# board.net
KiCad netlist of a schematic drawn in EAGLE
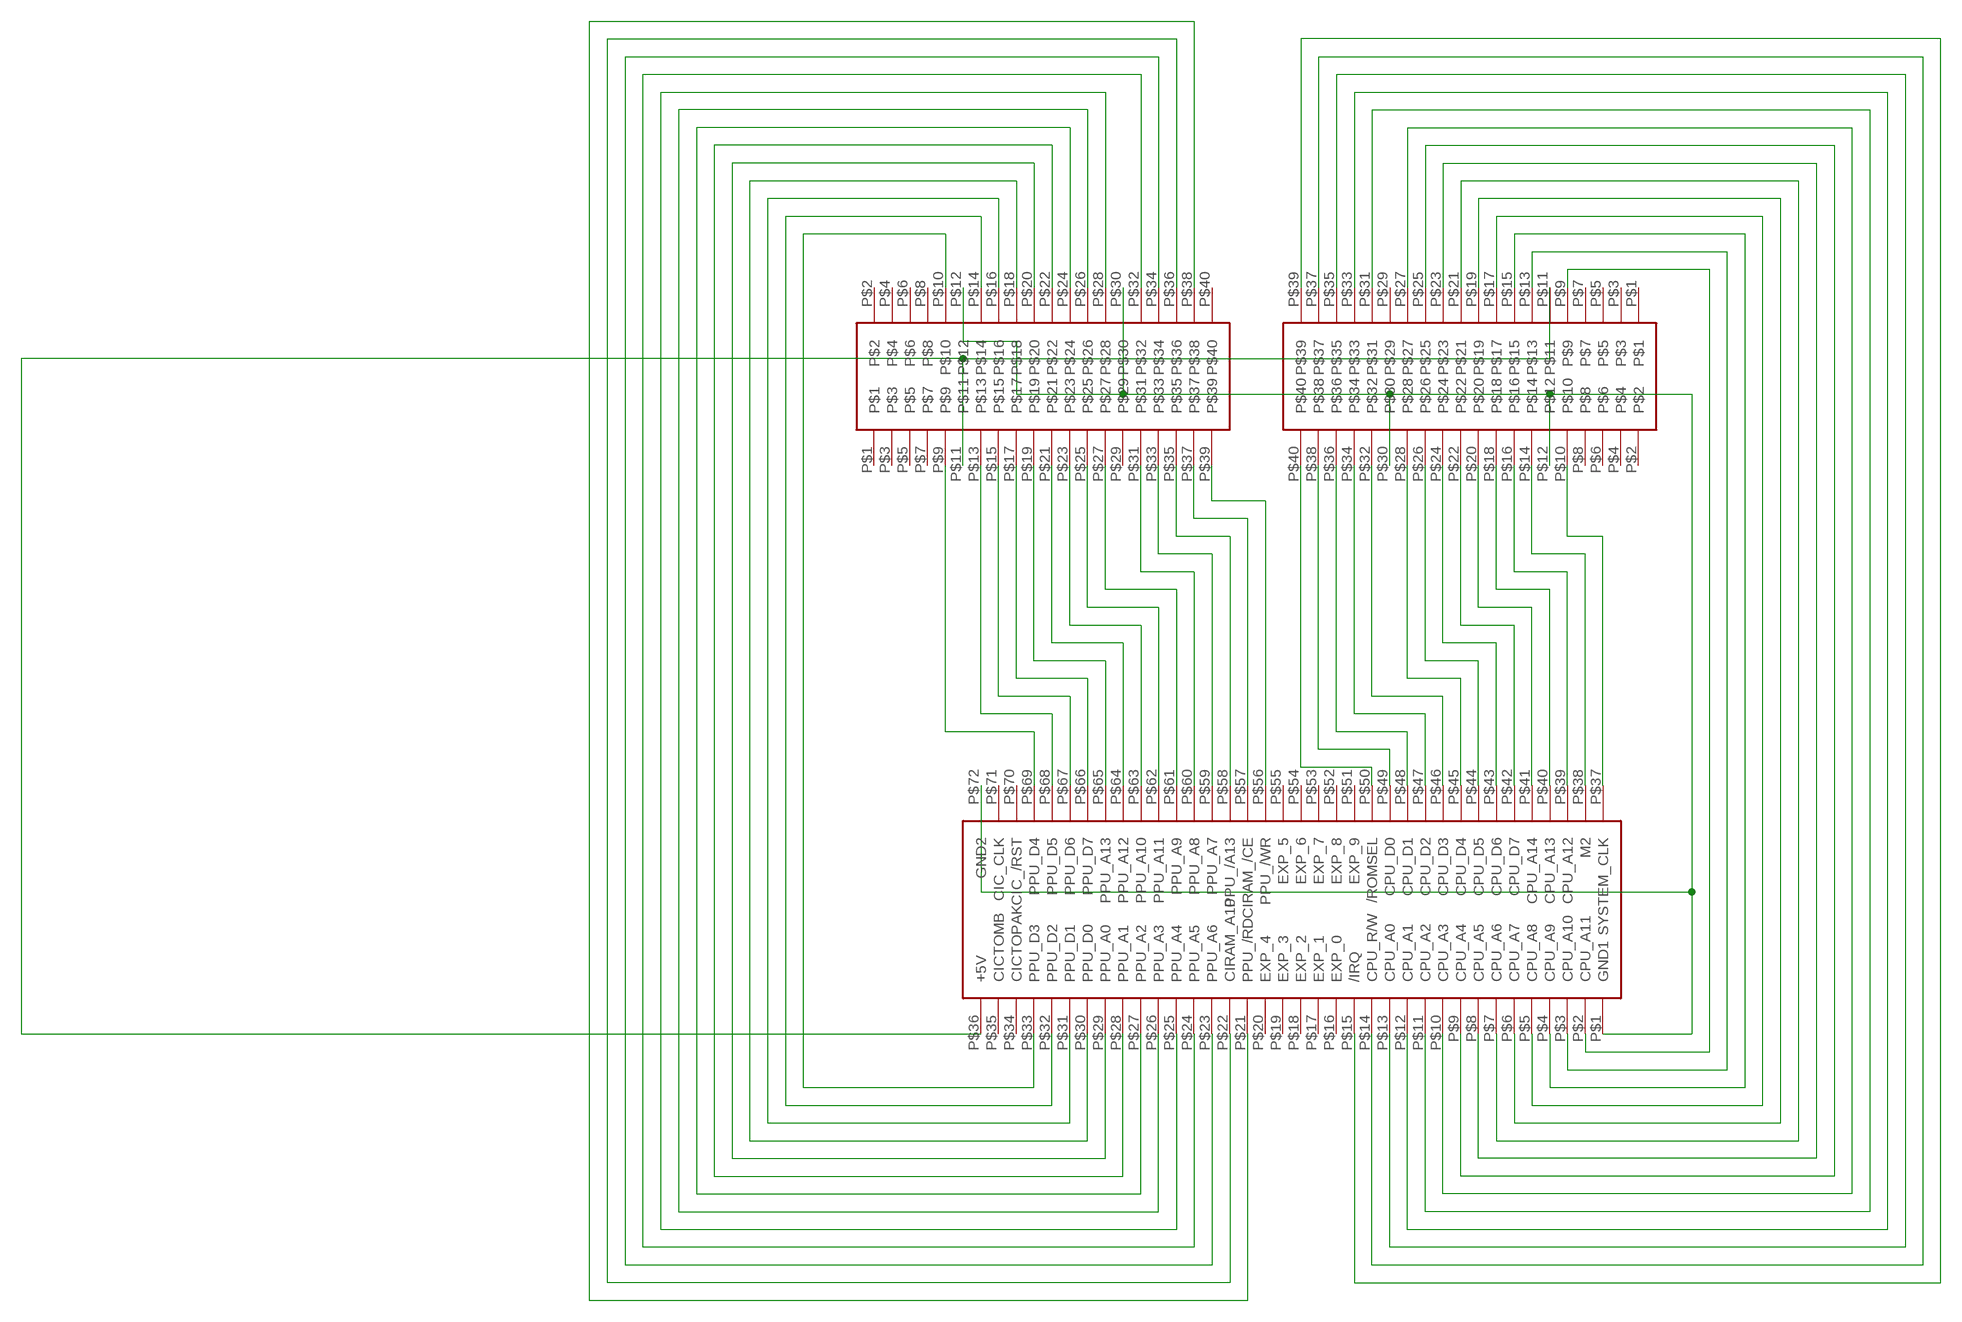
[diagram p0: schematic, sheet 1]

(export (version "E")
  (design (tool "Eeschema 10.0.6"))
  (components
    (comp (ref "U$1")
      (value "NES_CONN")
      (footprint "eagle-import:36X2")
      (libsource (lib "eagle-import") (part "NES_CONN"))
    )
    (comp (ref "U$2")
      (value "40PINNER")
      (footprint "eagle-import:40PINNER")
      (libsource (lib "eagle-import") (part "40PINNER"))
    )
    (comp (ref "U$3")
      (value "40PINNER")
      (footprint "eagle-import:40PINNER")
      (libsource (lib "eagle-import") (part "40PINNER"))
    )
  )
  (nets
    (net (code "1") (name "Net-(U$1-+5V)") (class "Default")
      (node (ref "U$1") (pin "P$36") (pinfunction "+5V_P$36") (pintype "bidirectional"))
      (node (ref "U$2") (pin "P$11") (pinfunction "P$11_P$11") (pintype "bidirectional"))
      (node (ref "U$3") (pin "P$11") (pinfunction "P$11_P$11") (pintype "bidirectional"))
    )
    (net (code "2") (name "Net-(U$1-CIRAM_A10)") (class "Default")
      (node (ref "U$1") (pin "P$22") (pinfunction "CIRAM_A10_P$22") (pintype "bidirectional"))
      (node (ref "U$2") (pin "P$36") (pinfunction "P$36_P$36") (pintype "bidirectional"))
    )
    (net (code "3") (name "Net-(U$1-CIRAM_{slash}CE)") (class "Default")
      (node (ref "U$1") (pin "P$57") (pinfunction "CIRAM_/CE_P$57") (pintype "bidirectional"))
      (node (ref "U$2") (pin "P$37") (pinfunction "P$37_P$37") (pintype "bidirectional"))
    )
    (net (code "4") (name "Net-(U$1-CPU_A0)") (class "Default")
      (node (ref "U$1") (pin "P$13") (pinfunction "CPU_A0_P$13") (pintype "bidirectional"))
      (node (ref "U$3") (pin "P$35") (pinfunction "P$35_P$35") (pintype "bidirectional"))
    )
    (net (code "5") (name "Net-(U$1-CPU_A1)") (class "Default")
      (node (ref "U$1") (pin "P$12") (pinfunction "CPU_A1_P$12") (pintype "bidirectional"))
      (node (ref "U$3") (pin "P$33") (pinfunction "P$33_P$33") (pintype "bidirectional"))
    )
    (net (code "6") (name "Net-(U$1-CPU_A2)") (class "Default")
      (node (ref "U$1") (pin "P$11") (pinfunction "CPU_A2_P$11") (pintype "bidirectional"))
      (node (ref "U$3") (pin "P$31") (pinfunction "P$31_P$31") (pintype "bidirectional"))
    )
    (net (code "7") (name "Net-(U$1-CPU_A3)") (class "Default")
      (node (ref "U$1") (pin "P$10") (pinfunction "CPU_A3_P$10") (pintype "bidirectional"))
      (node (ref "U$3") (pin "P$27") (pinfunction "P$27_P$27") (pintype "bidirectional"))
    )
    (net (code "8") (name "Net-(U$1-CPU_A4)") (class "Default")
      (node (ref "U$1") (pin "P$9") (pinfunction "CPU_A4_P$9") (pintype "bidirectional"))
      (node (ref "U$3") (pin "P$25") (pinfunction "P$25_P$25") (pintype "bidirectional"))
    )
    (net (code "9") (name "Net-(U$1-CPU_A5)") (class "Default")
      (node (ref "U$1") (pin "P$8") (pinfunction "CPU_A5_P$8") (pintype "bidirectional"))
      (node (ref "U$3") (pin "P$23") (pinfunction "P$23_P$23") (pintype "bidirectional"))
    )
    (net (code "10") (name "Net-(U$1-CPU_A6)") (class "Default")
      (node (ref "U$1") (pin "P$7") (pinfunction "CPU_A6_P$7") (pintype "bidirectional"))
      (node (ref "U$3") (pin "P$21") (pinfunction "P$21_P$21") (pintype "bidirectional"))
    )
    (net (code "11") (name "Net-(U$1-CPU_A7)") (class "Default")
      (node (ref "U$1") (pin "P$6") (pinfunction "CPU_A7_P$6") (pintype "bidirectional"))
      (node (ref "U$3") (pin "P$19") (pinfunction "P$19_P$19") (pintype "bidirectional"))
    )
    (net (code "12") (name "Net-(U$1-CPU_A8)") (class "Default")
      (node (ref "U$1") (pin "P$5") (pinfunction "CPU_A8_P$5") (pintype "bidirectional"))
      (node (ref "U$3") (pin "P$17") (pinfunction "P$17_P$17") (pintype "bidirectional"))
    )
    (net (code "13") (name "Net-(U$1-CPU_A9)") (class "Default")
      (node (ref "U$1") (pin "P$4") (pinfunction "CPU_A9_P$4") (pintype "bidirectional"))
      (node (ref "U$3") (pin "P$15") (pinfunction "P$15_P$15") (pintype "bidirectional"))
    )
    (net (code "14") (name "Net-(U$1-CPU_A10)") (class "Default")
      (node (ref "U$1") (pin "P$3") (pinfunction "CPU_A10_P$3") (pintype "bidirectional"))
      (node (ref "U$3") (pin "P$13") (pinfunction "P$13_P$13") (pintype "bidirectional"))
    )
    (net (code "15") (name "Net-(U$1-CPU_A11)") (class "Default")
      (node (ref "U$1") (pin "P$2") (pinfunction "CPU_A11_P$2") (pintype "bidirectional"))
      (node (ref "U$3") (pin "P$9") (pinfunction "P$9_P$9") (pintype "bidirectional"))
    )
    (net (code "16") (name "Net-(U$1-CPU_A12)") (class "Default")
      (node (ref "U$1") (pin "P$39") (pinfunction "CPU_A12_P$39") (pintype "bidirectional"))
      (node (ref "U$3") (pin "P$16") (pinfunction "P$16_P$16") (pintype "bidirectional"))
    )
    (net (code "17") (name "Net-(U$1-CPU_A13)") (class "Default")
      (node (ref "U$1") (pin "P$40") (pinfunction "CPU_A13_P$40") (pintype "bidirectional"))
      (node (ref "U$3") (pin "P$18") (pinfunction "P$18_P$18") (pintype "bidirectional"))
    )
    (net (code "18") (name "Net-(U$1-CPU_A14)") (class "Default")
      (node (ref "U$1") (pin "P$41") (pinfunction "CPU_A14_P$41") (pintype "bidirectional"))
      (node (ref "U$3") (pin "P$20") (pinfunction "P$20_P$20") (pintype "bidirectional"))
    )
    (net (code "19") (name "Net-(U$1-CPU_D0)") (class "Default")
      (node (ref "U$1") (pin "P$49") (pinfunction "CPU_D0_P$49") (pintype "bidirectional"))
      (node (ref "U$3") (pin "P$38") (pinfunction "P$38_P$38") (pintype "bidirectional"))
    )
    (net (code "20") (name "Net-(U$1-CPU_D1)") (class "Default")
      (node (ref "U$1") (pin "P$48") (pinfunction "CPU_D1_P$48") (pintype "bidirectional"))
      (node (ref "U$3") (pin "P$36") (pinfunction "P$36_P$36") (pintype "bidirectional"))
    )
    (net (code "21") (name "Net-(U$1-CPU_D2)") (class "Default")
      (node (ref "U$1") (pin "P$47") (pinfunction "CPU_D2_P$47") (pintype "bidirectional"))
      (node (ref "U$3") (pin "P$34") (pinfunction "P$34_P$34") (pintype "bidirectional"))
    )
    (net (code "22") (name "Net-(U$1-CPU_D3)") (class "Default")
      (node (ref "U$1") (pin "P$46") (pinfunction "CPU_D3_P$46") (pintype "bidirectional"))
      (node (ref "U$3") (pin "P$32") (pinfunction "P$32_P$32") (pintype "bidirectional"))
    )
    (net (code "23") (name "Net-(U$1-CPU_D4)") (class "Default")
      (node (ref "U$1") (pin "P$45") (pinfunction "CPU_D4_P$45") (pintype "bidirectional"))
      (node (ref "U$3") (pin "P$28") (pinfunction "P$28_P$28") (pintype "bidirectional"))
    )
    (net (code "24") (name "Net-(U$1-CPU_D5)") (class "Default")
      (node (ref "U$1") (pin "P$44") (pinfunction "CPU_D5_P$44") (pintype "bidirectional"))
      (node (ref "U$3") (pin "P$26") (pinfunction "P$26_P$26") (pintype "bidirectional"))
    )
    (net (code "25") (name "Net-(U$1-CPU_D6)") (class "Default")
      (node (ref "U$1") (pin "P$43") (pinfunction "CPU_D6_P$43") (pintype "bidirectional"))
      (node (ref "U$3") (pin "P$24") (pinfunction "P$24_P$24") (pintype "bidirectional"))
    )
    (net (code "26") (name "Net-(U$1-CPU_D7)") (class "Default")
      (node (ref "U$1") (pin "P$42") (pinfunction "CPU_D7_P$42") (pintype "bidirectional"))
      (node (ref "U$3") (pin "P$22") (pinfunction "P$22_P$22") (pintype "bidirectional"))
    )
    (net (code "27") (name "Net-(U$1-CPU_R{slash}W)") (class "Default")
      (node (ref "U$1") (pin "P$14") (pinfunction "CPU_R/W_P$14") (pintype "bidirectional"))
      (node (ref "U$3") (pin "P$37") (pinfunction "P$37_P$37") (pintype "bidirectional"))
    )
    (net (code "28") (name "Net-(U$1-GND1)") (class "Default")
      (node (ref "U$1") (pin "P$1") (pinfunction "GND1_P$1") (pintype "bidirectional"))
      (node (ref "U$1") (pin "P$72") (pinfunction "GND2_P$72") (pintype "bidirectional"))
      (node (ref "U$2") (pin "P$12") (pinfunction "P$12_P$12") (pintype "bidirectional"))
      (node (ref "U$2") (pin "P$30") (pinfunction "P$30_P$30") (pintype "bidirectional"))
      (node (ref "U$3") (pin "P$12") (pinfunction "P$12_P$12") (pintype "bidirectional"))
      (node (ref "U$3") (pin "P$30") (pinfunction "P$30_P$30") (pintype "bidirectional"))
    )
    (net (code "29") (name "Net-(U$1-M2)") (class "Default")
      (node (ref "U$1") (pin "P$38") (pinfunction "M2_P$38") (pintype "bidirectional"))
      (node (ref "U$3") (pin "P$14") (pinfunction "P$14_P$14") (pintype "bidirectional"))
    )
    (net (code "30") (name "Net-(U$1-PPU_A0)") (class "Default")
      (node (ref "U$1") (pin "P$29") (pinfunction "PPU_A0_P$29") (pintype "bidirectional"))
      (node (ref "U$2") (pin "P$20") (pinfunction "P$20_P$20") (pintype "bidirectional"))
    )
    (net (code "31") (name "Net-(U$1-PPU_A1)") (class "Default")
      (node (ref "U$1") (pin "P$28") (pinfunction "PPU_A1_P$28") (pintype "bidirectional"))
      (node (ref "U$2") (pin "P$22") (pinfunction "P$22_P$22") (pintype "bidirectional"))
    )
    (net (code "32") (name "Net-(U$1-PPU_A2)") (class "Default")
      (node (ref "U$1") (pin "P$27") (pinfunction "PPU_A2_P$27") (pintype "bidirectional"))
      (node (ref "U$2") (pin "P$24") (pinfunction "P$24_P$24") (pintype "bidirectional"))
    )
    (net (code "33") (name "Net-(U$1-PPU_A3)") (class "Default")
      (node (ref "U$1") (pin "P$26") (pinfunction "PPU_A3_P$26") (pintype "bidirectional"))
      (node (ref "U$2") (pin "P$26") (pinfunction "P$26_P$26") (pintype "bidirectional"))
    )
    (net (code "34") (name "Net-(U$1-PPU_A4)") (class "Default")
      (node (ref "U$1") (pin "P$25") (pinfunction "PPU_A4_P$25") (pintype "bidirectional"))
      (node (ref "U$2") (pin "P$28") (pinfunction "P$28_P$28") (pintype "bidirectional"))
    )
    (net (code "35") (name "Net-(U$1-PPU_A5)") (class "Default")
      (node (ref "U$1") (pin "P$24") (pinfunction "PPU_A5_P$24") (pintype "bidirectional"))
      (node (ref "U$2") (pin "P$32") (pinfunction "P$32_P$32") (pintype "bidirectional"))
    )
    (net (code "36") (name "Net-(U$1-PPU_A6)") (class "Default")
      (node (ref "U$1") (pin "P$23") (pinfunction "PPU_A6_P$23") (pintype "bidirectional"))
      (node (ref "U$2") (pin "P$34") (pinfunction "P$34_P$34") (pintype "bidirectional"))
    )
    (net (code "37") (name "Net-(U$1-PPU_A7)") (class "Default")
      (node (ref "U$1") (pin "P$59") (pinfunction "PPU_A7_P$59") (pintype "bidirectional"))
      (node (ref "U$2") (pin "P$33") (pinfunction "P$33_P$33") (pintype "bidirectional"))
    )
    (net (code "38") (name "Net-(U$1-PPU_A8)") (class "Default")
      (node (ref "U$1") (pin "P$60") (pinfunction "PPU_A8_P$60") (pintype "bidirectional"))
      (node (ref "U$2") (pin "P$31") (pinfunction "P$31_P$31") (pintype "bidirectional"))
    )
    (net (code "39") (name "Net-(U$1-PPU_A9)") (class "Default")
      (node (ref "U$1") (pin "P$61") (pinfunction "PPU_A9_P$61") (pintype "bidirectional"))
      (node (ref "U$2") (pin "P$27") (pinfunction "P$27_P$27") (pintype "bidirectional"))
    )
    (net (code "40") (name "Net-(U$1-PPU_A10)") (class "Default")
      (node (ref "U$1") (pin "P$63") (pinfunction "PPU_A10_P$63") (pintype "bidirectional"))
      (node (ref "U$2") (pin "P$23") (pinfunction "P$23_P$23") (pintype "bidirectional"))
    )
    (net (code "41") (name "Net-(U$1-PPU_A11)") (class "Default")
      (node (ref "U$1") (pin "P$62") (pinfunction "PPU_A11_P$62") (pintype "bidirectional"))
      (node (ref "U$2") (pin "P$25") (pinfunction "P$25_P$25") (pintype "bidirectional"))
    )
    (net (code "42") (name "Net-(U$1-PPU_A12)") (class "Default")
      (node (ref "U$1") (pin "P$64") (pinfunction "PPU_A12_P$64") (pintype "bidirectional"))
      (node (ref "U$2") (pin "P$21") (pinfunction "P$21_P$21") (pintype "bidirectional"))
    )
    (net (code "43") (name "Net-(U$1-PPU_A13)") (class "Default")
      (node (ref "U$1") (pin "P$65") (pinfunction "PPU_A13_P$65") (pintype "bidirectional"))
      (node (ref "U$2") (pin "P$19") (pinfunction "P$19_P$19") (pintype "bidirectional"))
    )
    (net (code "44") (name "Net-(U$1-PPU_D0)") (class "Default")
      (node (ref "U$1") (pin "P$30") (pinfunction "PPU_D0_P$30") (pintype "bidirectional"))
      (node (ref "U$2") (pin "P$18") (pinfunction "P$18_P$18") (pintype "bidirectional"))
    )
    (net (code "45") (name "Net-(U$1-PPU_D1)") (class "Default")
      (node (ref "U$1") (pin "P$31") (pinfunction "PPU_D1_P$31") (pintype "bidirectional"))
      (node (ref "U$2") (pin "P$16") (pinfunction "P$16_P$16") (pintype "bidirectional"))
    )
    (net (code "46") (name "Net-(U$1-PPU_D2)") (class "Default")
      (node (ref "U$1") (pin "P$32") (pinfunction "PPU_D2_P$32") (pintype "bidirectional"))
      (node (ref "U$2") (pin "P$14") (pinfunction "P$14_P$14") (pintype "bidirectional"))
    )
    (net (code "47") (name "Net-(U$1-PPU_D3)") (class "Default")
      (node (ref "U$1") (pin "P$33") (pinfunction "PPU_D3_P$33") (pintype "bidirectional"))
      (node (ref "U$2") (pin "P$10") (pinfunction "P$10_P$10") (pintype "bidirectional"))
    )
    (net (code "48") (name "Net-(U$1-PPU_D4)") (class "Default")
      (node (ref "U$1") (pin "P$69") (pinfunction "PPU_D4_P$69") (pintype "bidirectional"))
      (node (ref "U$2") (pin "P$9") (pinfunction "P$9_P$9") (pintype "bidirectional"))
    )
    (net (code "49") (name "Net-(U$1-PPU_D5)") (class "Default")
      (node (ref "U$1") (pin "P$68") (pinfunction "PPU_D5_P$68") (pintype "bidirectional"))
      (node (ref "U$2") (pin "P$13") (pinfunction "P$13_P$13") (pintype "bidirectional"))
    )
    (net (code "50") (name "Net-(U$1-PPU_D6)") (class "Default")
      (node (ref "U$1") (pin "P$67") (pinfunction "PPU_D6_P$67") (pintype "bidirectional"))
      (node (ref "U$2") (pin "P$15") (pinfunction "P$15_P$15") (pintype "bidirectional"))
    )
    (net (code "51") (name "Net-(U$1-PPU_D7)") (class "Default")
      (node (ref "U$1") (pin "P$66") (pinfunction "PPU_D7_P$66") (pintype "bidirectional"))
      (node (ref "U$2") (pin "P$17") (pinfunction "P$17_P$17") (pintype "bidirectional"))
    )
    (net (code "52") (name "Net-(U$1-PPU_{slash}A13)") (class "Default")
      (node (ref "U$1") (pin "P$58") (pinfunction "PPU_/A13_P$58") (pintype "bidirectional"))
      (node (ref "U$2") (pin "P$35") (pinfunction "P$35_P$35") (pintype "bidirectional"))
    )
    (net (code "53") (name "Net-(U$1-PPU_{slash}RD)") (class "Default")
      (node (ref "U$1") (pin "P$21") (pinfunction "PPU_/RD_P$21") (pintype "bidirectional"))
      (node (ref "U$2") (pin "P$38") (pinfunction "P$38_P$38") (pintype "bidirectional"))
    )
    (net (code "54") (name "Net-(U$1-PPU_{slash}WR)") (class "Default")
      (node (ref "U$1") (pin "P$56") (pinfunction "PPU_/WR_P$56") (pintype "bidirectional"))
      (node (ref "U$2") (pin "P$39") (pinfunction "P$39_P$39") (pintype "bidirectional"))
    )
    (net (code "55") (name "Net-(U$1-SYSTEM_CLK)") (class "Default")
      (node (ref "U$1") (pin "P$37") (pinfunction "SYSTEM_CLK_P$37") (pintype "bidirectional"))
      (node (ref "U$3") (pin "P$10") (pinfunction "P$10_P$10") (pintype "bidirectional"))
    )
    (net (code "56") (name "Net-(U$1-{slash}IRQ)") (class "Default")
      (node (ref "U$1") (pin "P$15") (pinfunction "/IRQ_P$15") (pintype "bidirectional"))
      (node (ref "U$3") (pin "P$39") (pinfunction "P$39_P$39") (pintype "bidirectional"))
    )
    (net (code "57") (name "Net-(U$1-{slash}ROMSEL)") (class "Default")
      (node (ref "U$1") (pin "P$50") (pinfunction "/ROMSEL_P$50") (pintype "bidirectional"))
      (node (ref "U$3") (pin "P$40") (pinfunction "P$40_P$40") (pintype "bidirectional"))
    )
    (net (code "58") (name "unconnected-(U$1-CICTOMB-PadP$35)") (class "Default")
      (node (ref "U$1") (pin "P$35") (pinfunction "CICTOMB_P$35") (pintype "bidirectional"))
    )
    (net (code "59") (name "unconnected-(U$1-CICTOPAK-PadP$34)") (class "Default")
      (node (ref "U$1") (pin "P$34") (pinfunction "CICTOPAK_P$34") (pintype "bidirectional"))
    )
    (net (code "60") (name "unconnected-(U$1-CIC_CLK-PadP$71)") (class "Default")
      (node (ref "U$1") (pin "P$71") (pinfunction "CIC_CLK_P$71") (pintype "bidirectional"))
    )
    (net (code "61") (name "unconnected-(U$1-CIC_{slash}RST-PadP$70)") (class "Default")
      (node (ref "U$1") (pin "P$70") (pinfunction "CIC_/RST_P$70") (pintype "bidirectional"))
    )
    (net (code "62") (name "unconnected-(U$1-EXP_0-PadP$16)") (class "Default")
      (node (ref "U$1") (pin "P$16") (pinfunction "EXP_0_P$16") (pintype "bidirectional"))
    )
    (net (code "63") (name "unconnected-(U$1-EXP_1-PadP$17)") (class "Default")
      (node (ref "U$1") (pin "P$17") (pinfunction "EXP_1_P$17") (pintype "bidirectional"))
    )
    (net (code "64") (name "unconnected-(U$1-EXP_2-PadP$18)") (class "Default")
      (node (ref "U$1") (pin "P$18") (pinfunction "EXP_2_P$18") (pintype "bidirectional"))
    )
    (net (code "65") (name "unconnected-(U$1-EXP_3-PadP$19)") (class "Default")
      (node (ref "U$1") (pin "P$19") (pinfunction "EXP_3_P$19") (pintype "bidirectional"))
    )
    (net (code "66") (name "unconnected-(U$1-EXP_4-PadP$20)") (class "Default")
      (node (ref "U$1") (pin "P$20") (pinfunction "EXP_4_P$20") (pintype "bidirectional"))
    )
    (net (code "67") (name "unconnected-(U$1-EXP_5-PadP$55)") (class "Default")
      (node (ref "U$1") (pin "P$55") (pinfunction "EXP_5_P$55") (pintype "bidirectional"))
    )
    (net (code "68") (name "unconnected-(U$1-EXP_6-PadP$54)") (class "Default")
      (node (ref "U$1") (pin "P$54") (pinfunction "EXP_6_P$54") (pintype "bidirectional"))
    )
    (net (code "69") (name "unconnected-(U$1-EXP_7-PadP$53)") (class "Default")
      (node (ref "U$1") (pin "P$53") (pinfunction "EXP_7_P$53") (pintype "bidirectional"))
    )
    (net (code "70") (name "unconnected-(U$1-EXP_8-PadP$52)") (class "Default")
      (node (ref "U$1") (pin "P$52") (pinfunction "EXP_8_P$52") (pintype "bidirectional"))
    )
    (net (code "71") (name "unconnected-(U$1-EXP_9-PadP$51)") (class "Default")
      (node (ref "U$1") (pin "P$51") (pinfunction "EXP_9_P$51") (pintype "bidirectional"))
    )
    (net (code "72") (name "unconnected-(U$2-PadP$1)") (class "Default")
      (node (ref "U$2") (pin "P$1") (pinfunction "P$1_P$1") (pintype "bidirectional"))
    )
    (net (code "73") (name "unconnected-(U$2-PadP$2)") (class "Default")
      (node (ref "U$2") (pin "P$2") (pinfunction "P$2_P$2") (pintype "bidirectional"))
    )
    (net (code "74") (name "unconnected-(U$2-PadP$3)") (class "Default")
      (node (ref "U$2") (pin "P$3") (pinfunction "P$3_P$3") (pintype "bidirectional"))
    )
    (net (code "75") (name "unconnected-(U$2-PadP$4)") (class "Default")
      (node (ref "U$2") (pin "P$4") (pinfunction "P$4_P$4") (pintype "bidirectional"))
    )
    (net (code "76") (name "unconnected-(U$2-PadP$5)") (class "Default")
      (node (ref "U$2") (pin "P$5") (pinfunction "P$5_P$5") (pintype "bidirectional"))
    )
    (net (code "77") (name "unconnected-(U$2-PadP$6)") (class "Default")
      (node (ref "U$2") (pin "P$6") (pinfunction "P$6_P$6") (pintype "bidirectional"))
    )
    (net (code "78") (name "unconnected-(U$2-PadP$7)") (class "Default")
      (node (ref "U$2") (pin "P$7") (pinfunction "P$7_P$7") (pintype "bidirectional"))
    )
    (net (code "79") (name "unconnected-(U$2-PadP$8)") (class "Default")
      (node (ref "U$2") (pin "P$8") (pinfunction "P$8_P$8") (pintype "bidirectional"))
    )
    (net (code "80") (name "unconnected-(U$2-PadP$29)") (class "Default")
      (node (ref "U$2") (pin "P$29") (pinfunction "P$29_P$29") (pintype "bidirectional"))
    )
    (net (code "81") (name "unconnected-(U$2-PadP$40)") (class "Default")
      (node (ref "U$2") (pin "P$40") (pinfunction "P$40_P$40") (pintype "bidirectional"))
    )
    (net (code "82") (name "unconnected-(U$3-PadP$1)") (class "Default")
      (node (ref "U$3") (pin "P$1") (pinfunction "P$1_P$1") (pintype "bidirectional"))
    )
    (net (code "83") (name "unconnected-(U$3-PadP$2)") (class "Default")
      (node (ref "U$3") (pin "P$2") (pinfunction "P$2_P$2") (pintype "bidirectional"))
    )
    (net (code "84") (name "unconnected-(U$3-PadP$3)") (class "Default")
      (node (ref "U$3") (pin "P$3") (pinfunction "P$3_P$3") (pintype "bidirectional"))
    )
    (net (code "85") (name "unconnected-(U$3-PadP$4)") (class "Default")
      (node (ref "U$3") (pin "P$4") (pinfunction "P$4_P$4") (pintype "bidirectional"))
    )
    (net (code "86") (name "unconnected-(U$3-PadP$5)") (class "Default")
      (node (ref "U$3") (pin "P$5") (pinfunction "P$5_P$5") (pintype "bidirectional"))
    )
    (net (code "87") (name "unconnected-(U$3-PadP$6)") (class "Default")
      (node (ref "U$3") (pin "P$6") (pinfunction "P$6_P$6") (pintype "bidirectional"))
    )
    (net (code "88") (name "unconnected-(U$3-PadP$7)") (class "Default")
      (node (ref "U$3") (pin "P$7") (pinfunction "P$7_P$7") (pintype "bidirectional"))
    )
    (net (code "89") (name "unconnected-(U$3-PadP$8)") (class "Default")
      (node (ref "U$3") (pin "P$8") (pinfunction "P$8_P$8") (pintype "bidirectional"))
    )
    (net (code "90") (name "unconnected-(U$3-PadP$29)") (class "Default")
      (node (ref "U$3") (pin "P$29") (pinfunction "P$29_P$29") (pintype "bidirectional"))
    )
  )
)
